# 11ethernetGbit.net
KiCad netlist of a schematic drawn in Altium Designer
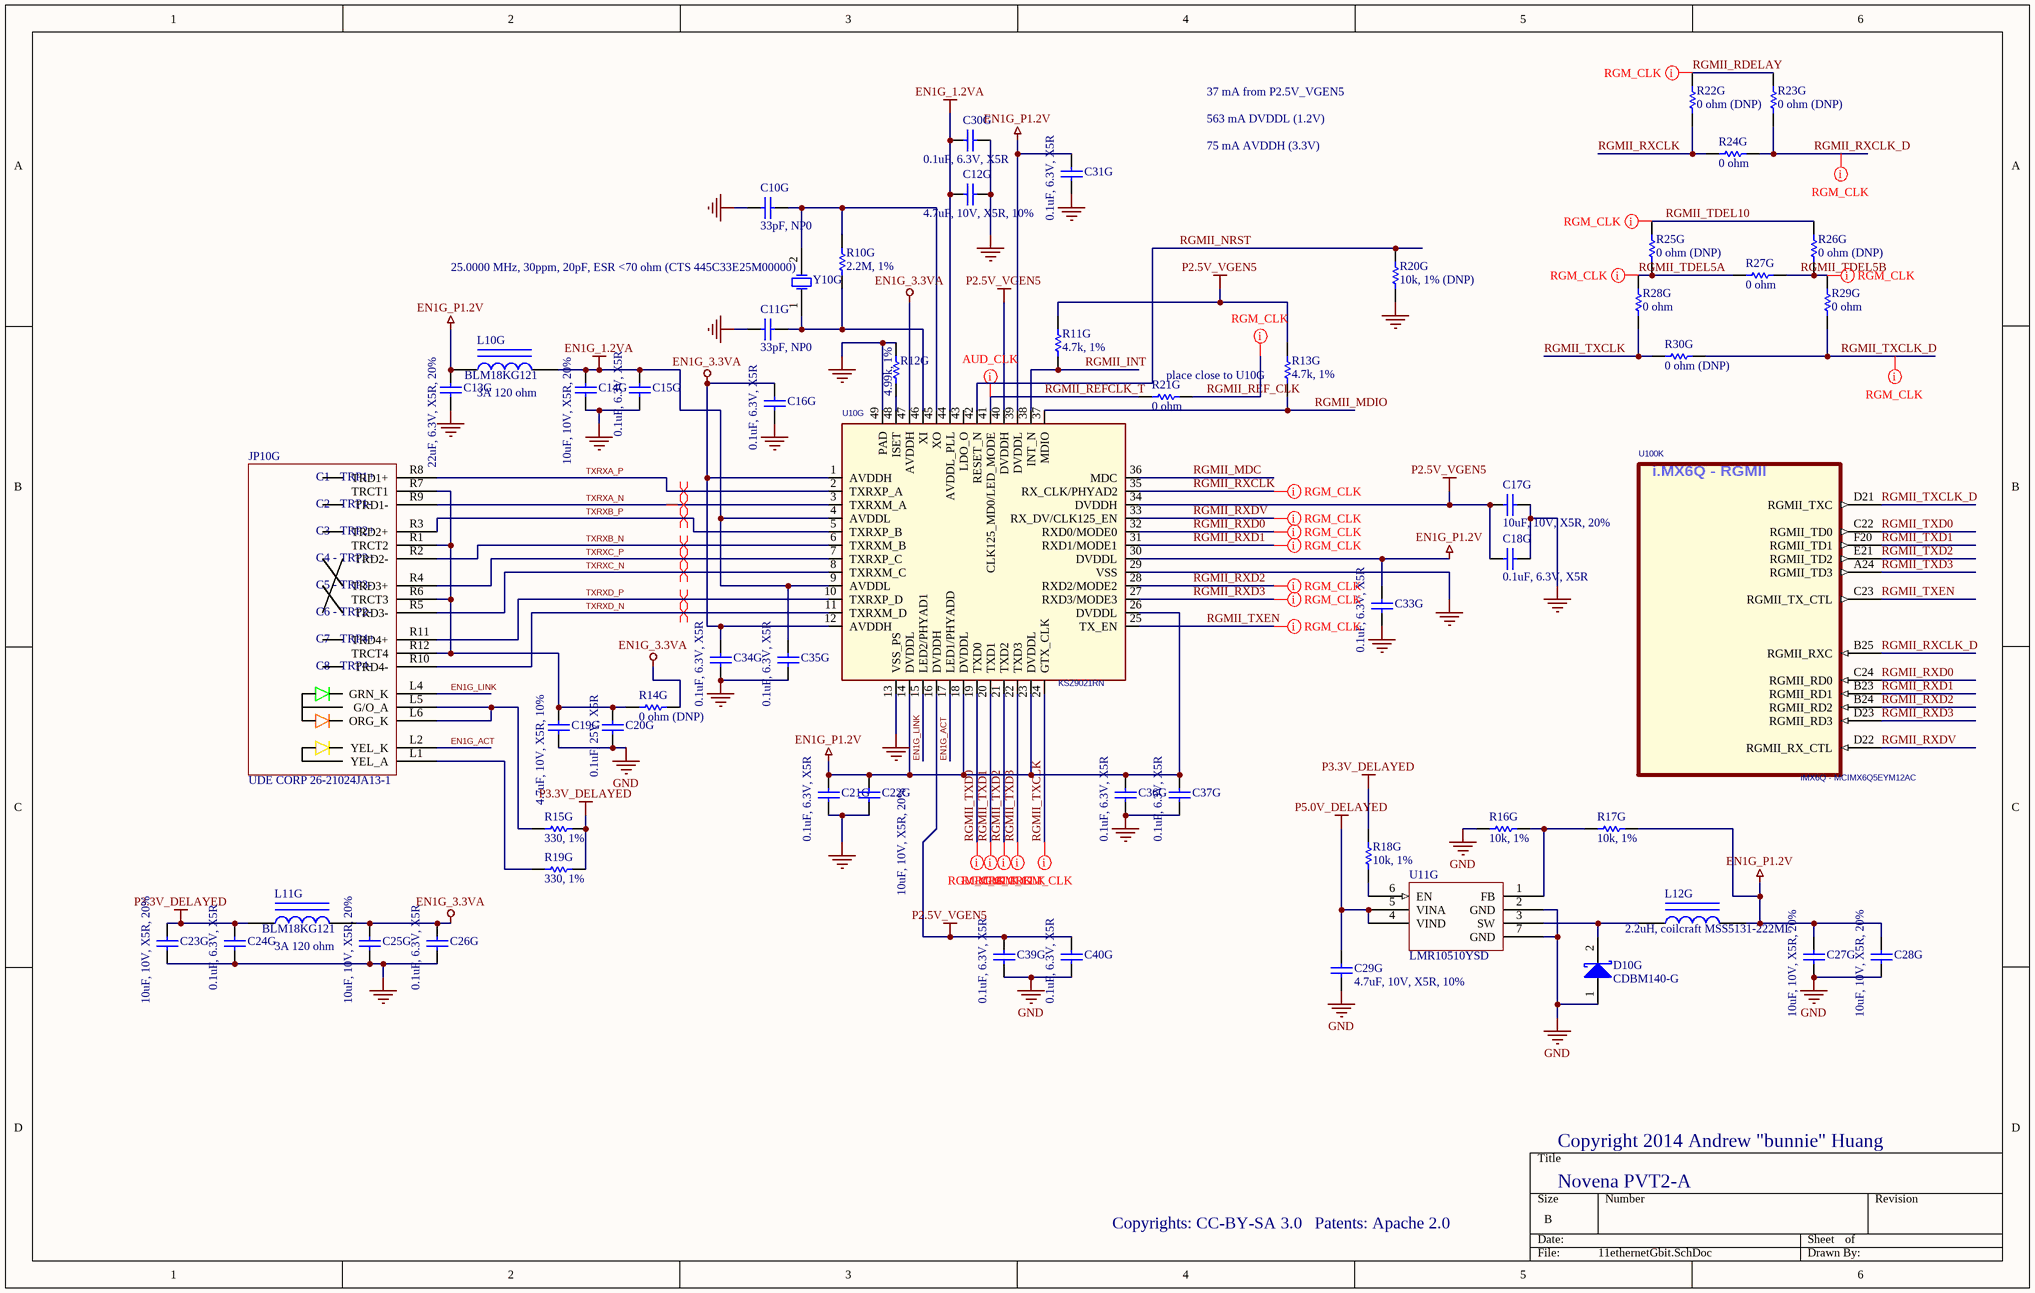
[diagram p0: 11ethernetGbit.SchDoc]

(export (version "E")
  (design (tool "Eeschema 10.0.6"))
  (components
    (comp (ref "C10G")
      (value "33pF, NP0")
      (footprint "CAPC1005N")
      (description "Capacitor (Semiconductor SIM Model)")
      (fields (field (name "PUBLISHER") "Altium Limited"))
      (libsource (lib "Miscellaneous Devices") (part "Cap Semi"))
    )
    (comp (ref "C11G")
      (value "33pF, NP0")
      (footprint "CAPC1005N")
      (description "Capacitor (Semiconductor SIM Model)")
      (fields (field (name "PUBLISHER") "Altium Limited"))
      (libsource (lib "Miscellaneous Devices") (part "Cap Semi"))
    )
    (comp (ref "C12G")
      (value "4.7uF, 10V, X5R, 10%")
      (footprint "CAPC1608N")
      (description "Capacitor (Semiconductor SIM Model)")
      (fields (field (name "PUBLISHER") "Altium Limited"))
      (libsource (lib "Miscellaneous Devices") (part "Cap Semi"))
    )
    (comp (ref "C13G")
      (value "22uF, 6.3V, X5R, 20%")
      (footprint "CAPC1608N_HD")
      (description "Capacitor (Semiconductor SIM Model)")
      (fields (field (name "PUBLISHER") "Altium Limited"))
      (libsource (lib "Miscellaneous Devices") (part "Cap Semi"))
    )
    (comp (ref "C14G")
      (value "10uF, 10V, X5R, 20%")
      (footprint "CAPC1608N")
      (description "Capacitor (Semiconductor SIM Model)")
      (fields (field (name "PUBLISHER") "Altium Limited"))
      (libsource (lib "Miscellaneous Devices") (part "Cap Semi"))
    )
    (comp (ref "C15G")
      (value "0.1uF, 6.3V, X5R")
      (footprint "CAPC0603N_B")
      (description "Capacitor (Semiconductor SIM Model)")
      (fields (field (name "PUBLISHER") "Altium Limited"))
      (libsource (lib "Miscellaneous Devices") (part "Cap Semi"))
    )
    (comp (ref "C16G")
      (value "0.1uF, 6.3V, X5R")
      (footprint "CAPC0603N_B")
      (description "Capacitor (Semiconductor SIM Model)")
      (fields (field (name "PUBLISHER") "Altium Limited"))
      (libsource (lib "Miscellaneous Devices") (part "Cap Semi"))
    )
    (comp (ref "C17G")
      (value "10uF, 10V, X5R, 20%")
      (footprint "CAPC1608N")
      (description "Capacitor (Semiconductor SIM Model)")
      (fields (field (name "PUBLISHER") "Altium Limited"))
      (libsource (lib "Miscellaneous Devices") (part "Cap Semi"))
    )
    (comp (ref "C18G")
      (value "0.1uF, 6.3V, X5R")
      (footprint "CAPC0603N_B")
      (description "Capacitor (Semiconductor SIM Model)")
      (fields (field (name "PUBLISHER") "Altium Limited"))
      (libsource (lib "Miscellaneous Devices") (part "Cap Semi"))
    )
    (comp (ref "C19G")
      (value "4.7uF, 10V, X5R, 10%")
      (footprint "CAPC1608N")
      (description "Capacitor (Semiconductor SIM Model)")
      (fields (field (name "PUBLISHER") "Altium Limited"))
      (libsource (lib "Miscellaneous Devices") (part "Cap Semi"))
    )
    (comp (ref "C20G")
      (value "0.1uF, 25V, X5R")
      (footprint "CAPC1005N")
      (description "Capacitor (Semiconductor SIM Model)")
      (fields (field (name "PUBLISHER") "Altium Limited"))
      (libsource (lib "Miscellaneous Devices") (part "Cap Semi"))
    )
    (comp (ref "C21G")
      (value "0.1uF, 6.3V, X5R")
      (footprint "CAPC0603N_B")
      (description "Capacitor (Semiconductor SIM Model)")
      (fields (field (name "PUBLISHER") "Altium Limited"))
      (libsource (lib "Miscellaneous Devices") (part "Cap Semi"))
    )
    (comp (ref "C22G")
      (value "10uF, 10V, X5R, 20%")
      (footprint "CAPC1608N")
      (description "Capacitor (Semiconductor SIM Model)")
      (fields (field (name "PUBLISHER") "Altium Limited"))
      (libsource (lib "Miscellaneous Devices") (part "Cap Semi"))
    )
    (comp (ref "C23G")
      (value "10uF, 10V, X5R, 20%")
      (footprint "CAPC1608N")
      (description "Capacitor (Semiconductor SIM Model)")
      (fields (field (name "PUBLISHER") "Altium Limited"))
      (libsource (lib "Miscellaneous Devices") (part "Cap Semi"))
    )
    (comp (ref "C24G")
      (value "0.1uF, 6.3V, X5R")
      (footprint "CAPC0603N_B")
      (description "Capacitor (Semiconductor SIM Model)")
      (fields (field (name "PUBLISHER") "Altium Limited"))
      (libsource (lib "Miscellaneous Devices") (part "Cap Semi"))
    )
    (comp (ref "C25G")
      (value "10uF, 10V, X5R, 20%")
      (footprint "CAPC1608N")
      (description "Capacitor (Semiconductor SIM Model)")
      (fields (field (name "PUBLISHER") "Altium Limited"))
      (libsource (lib "Miscellaneous Devices") (part "Cap Semi"))
    )
    (comp (ref "C26G")
      (value "0.1uF, 6.3V, X5R")
      (footprint "CAPC0603N_B")
      (description "Capacitor (Semiconductor SIM Model)")
      (fields (field (name "PUBLISHER") "Altium Limited"))
      (libsource (lib "Miscellaneous Devices") (part "Cap Semi"))
    )
    (comp (ref "C27G")
      (value "10uF, 10V, X5R, 20%")
      (footprint "CAPC1608N")
      (description "Capacitor (Semiconductor SIM Model)")
      (fields (field (name "PUBLISHER") "Altium Limited"))
      (libsource (lib "Miscellaneous Devices") (part "Cap Semi"))
    )
    (comp (ref "C28G")
      (value "10uF, 10V, X5R, 20%")
      (footprint "CAPC1608N")
      (description "Capacitor (Semiconductor SIM Model)")
      (fields (field (name "PUBLISHER") "Altium Limited"))
      (libsource (lib "Miscellaneous Devices") (part "Cap Semi"))
    )
    (comp (ref "C29G")
      (value "4.7uF, 10V, X5R, 10%")
      (footprint "CAPC1608N")
      (description "Capacitor (Semiconductor SIM Model)")
      (fields (field (name "PUBLISHER") "Altium Limited"))
      (libsource (lib "Miscellaneous Devices") (part "Cap Semi"))
    )
    (comp (ref "C30G")
      (value "0.1uF, 6.3V, X5R")
      (footprint "CAPC0603N_B")
      (description "Capacitor (Semiconductor SIM Model)")
      (fields (field (name "PUBLISHER") "Altium Limited"))
      (libsource (lib "Miscellaneous Devices") (part "Cap Semi"))
    )
    (comp (ref "C31G")
      (value "0.1uF, 6.3V, X5R")
      (footprint "CAPC0603N_B")
      (description "Capacitor (Semiconductor SIM Model)")
      (fields (field (name "PUBLISHER") "Altium Limited"))
      (libsource (lib "Miscellaneous Devices") (part "Cap Semi"))
    )
    (comp (ref "C33G")
      (value "0.1uF, 6.3V, X5R")
      (footprint "CAPC0603N_B")
      (description "Capacitor (Semiconductor SIM Model)")
      (fields (field (name "PUBLISHER") "Altium Limited"))
      (libsource (lib "Miscellaneous Devices") (part "Cap Semi"))
    )
    (comp (ref "C34G")
      (value "0.1uF, 6.3V, X5R")
      (footprint "CAPC0603N_B")
      (description "Capacitor (Semiconductor SIM Model)")
      (fields (field (name "PUBLISHER") "Altium Limited"))
      (libsource (lib "Miscellaneous Devices") (part "Cap Semi"))
    )
    (comp (ref "C35G")
      (value "0.1uF, 6.3V, X5R")
      (footprint "CAPC0603N_B")
      (description "Capacitor (Semiconductor SIM Model)")
      (fields (field (name "PUBLISHER") "Altium Limited"))
      (libsource (lib "Miscellaneous Devices") (part "Cap Semi"))
    )
    (comp (ref "C36G")
      (value "0.1uF, 6.3V, X5R")
      (footprint "CAPC0603N_B")
      (description "Capacitor (Semiconductor SIM Model)")
      (fields (field (name "PUBLISHER") "Altium Limited"))
      (libsource (lib "Miscellaneous Devices") (part "Cap Semi"))
    )
    (comp (ref "C37G")
      (value "0.1uF, 6.3V, X5R")
      (footprint "CAPC0603N_B")
      (description "Capacitor (Semiconductor SIM Model)")
      (fields (field (name "PUBLISHER") "Altium Limited"))
      (libsource (lib "Miscellaneous Devices") (part "Cap Semi"))
    )
    (comp (ref "C39G")
      (value "0.1uF, 6.3V, X5R")
      (footprint "CAPC0603N_B")
      (description "Capacitor (Semiconductor SIM Model)")
      (fields (field (name "PUBLISHER") "Altium Limited"))
      (libsource (lib "Miscellaneous Devices") (part "Cap Semi"))
    )
    (comp (ref "C40G")
      (value "0.1uF, 6.3V, X5R")
      (footprint "CAPC0603N_B")
      (description "Capacitor (Semiconductor SIM Model)")
      (fields (field (name "PUBLISHER") "Altium Limited"))
      (libsource (lib "Miscellaneous Devices") (part "Cap Semi"))
    )
    (comp (ref "D10G")
      (value "CDBM140-G")
      (footprint "SOD123")
      (description "Schottky Diode")
      (fields (field (name "PUBLISHER") "Altium Limited"))
      (libsource (lib "Miscellaneous Devices") (part "D Schottky"))
    )
    (comp (ref "JP10G")
      (value "UDE CORP 26-21024JA13-1")
      (footprint "UDE_CORP_26-21024JA13-1")
      (description "10/100/1000BT + magnetics, symmetric, tab up, with LEDs")
      (libsource (lib "commonsch") (part "UDE_CORP_26-21024JA13-1"))
    )
    (comp (ref "L10G")
      (value "BLM18KG121")
      (footprint "INDC1608AN")
      (description "Magnetic-Core Inductor")
      (fields (field (name "ALTIUM_VALUE") "3A 120 ohm") (field (name "PUBLISHER") "Altium Limited"))
      (libsource (lib "Miscellaneous Devices") (part "Inductor Iron"))
    )
    (comp (ref "L11G")
      (value "BLM18KG121")
      (footprint "INDC1608AN")
      (description "Magnetic-Core Inductor")
      (fields (field (name "ALTIUM_VALUE") "3A 120 ohm") (field (name "PUBLISHER") "Altium Limited"))
      (libsource (lib "Miscellaneous Devices") (part "Inductor Iron"))
    )
    (comp (ref "L12G")
      (value "2.2uH, coilcraft MSS5131-222ML")
      (footprint "COILCRAFT_MSS5121")
      (description "Magnetic-Core Inductor")
      (fields (field (name "PUBLISHER") "Altium Limited"))
      (libsource (lib "Miscellaneous Devices") (part "Inductor Iron"))
    )
    (comp (ref "R10G")
      (value "2.2M, 1%")
      (footprint "RESC1005N")
      (description "Resistor")
      (fields (field (name "PUBLISHER") "Altium Limited"))
      (libsource (lib "Miscellaneous Devices") (part "Res1"))
    )
    (comp (ref "R11G")
      (value "4.7k, 1%")
      (footprint "RESC1005N")
      (description "Resistor")
      (fields (field (name "PUBLISHER") "Altium Limited"))
      (libsource (lib "Miscellaneous Devices") (part "Res1"))
    )
    (comp (ref "R12G")
      (value "4.99k, 1%")
      (footprint "RESC1005N")
      (description "Resistor")
      (fields (field (name "PUBLISHER") "Altium Limited"))
      (libsource (lib "Miscellaneous Devices") (part "Res1"))
    )
    (comp (ref "R13G")
      (value "4.7k, 1%")
      (footprint "RESC1005N")
      (description "Resistor")
      (fields (field (name "PUBLISHER") "Altium Limited"))
      (libsource (lib "Miscellaneous Devices") (part "Res1"))
    )
    (comp (ref "R14G")
      (value "0 ohm (DNP)")
      (footprint "RESC1005N")
      (description "Resistor")
      (fields (field (name "PUBLISHER") "Altium Limited"))
      (libsource (lib "Miscellaneous Devices") (part "Res1"))
    )
    (comp (ref "R15G")
      (value "330, 1%")
      (footprint "RESC1005N")
      (description "Resistor")
      (fields (field (name "PUBLISHER") "Altium Limited"))
      (libsource (lib "Miscellaneous Devices") (part "Res1"))
    )
    (comp (ref "R16G")
      (value "10k, 1%")
      (footprint "RESC1005N")
      (description "Resistor")
      (fields (field (name "PUBLISHER") "Altium Limited"))
      (libsource (lib "Miscellaneous Devices") (part "Res1"))
    )
    (comp (ref "R17G")
      (value "10k, 1%")
      (footprint "RESC1005N")
      (description "Resistor")
      (fields (field (name "PUBLISHER") "Altium Limited"))
      (libsource (lib "Miscellaneous Devices") (part "Res1"))
    )
    (comp (ref "R18G")
      (value "10k, 1%")
      (footprint "RESC1005N")
      (description "Resistor")
      (fields (field (name "PUBLISHER") "Altium Limited"))
      (libsource (lib "Miscellaneous Devices") (part "Res1"))
    )
    (comp (ref "R19G")
      (value "330, 1%")
      (footprint "RESC1005N")
      (description "Resistor")
      (fields (field (name "PUBLISHER") "Altium Limited"))
      (libsource (lib "Miscellaneous Devices") (part "Res1"))
    )
    (comp (ref "R20G")
      (value "10k, 1% (DNP)")
      (footprint "RESC1005N")
      (description "Resistor")
      (fields (field (name "PUBLISHER") "Altium Limited"))
      (libsource (lib "Miscellaneous Devices") (part "Res1"))
    )
    (comp (ref "R21G")
      (value "0 ohm")
      (footprint "RESC1005N")
      (description "Resistor")
      (fields (field (name "PUBLISHER") "Altium Limited"))
      (libsource (lib "Miscellaneous Devices") (part "Res1"))
    )
    (comp (ref "R22G")
      (value "0 ohm (DNP)")
      (footprint "RESC1005N")
      (description "Resistor")
      (fields (field (name "PUBLISHER") "Altium Limited"))
      (libsource (lib "Miscellaneous Devices") (part "Res1"))
    )
    (comp (ref "R23G")
      (value "0 ohm (DNP)")
      (footprint "RESC1005N")
      (description "Resistor")
      (fields (field (name "PUBLISHER") "Altium Limited"))
      (libsource (lib "Miscellaneous Devices") (part "Res1"))
    )
    (comp (ref "R24G")
      (value "0 ohm")
      (footprint "RESC1005N")
      (description "Resistor")
      (fields (field (name "PUBLISHER") "Altium Limited"))
      (libsource (lib "Miscellaneous Devices") (part "Res1"))
    )
    (comp (ref "R25G")
      (value "0 ohm (DNP)")
      (footprint "RESC1005N")
      (description "Resistor")
      (fields (field (name "PUBLISHER") "Altium Limited"))
      (libsource (lib "Miscellaneous Devices") (part "Res1"))
    )
    (comp (ref "R26G")
      (value "0 ohm (DNP)")
      (footprint "RESC1005N")
      (description "Resistor")
      (fields (field (name "PUBLISHER") "Altium Limited"))
      (libsource (lib "Miscellaneous Devices") (part "Res1"))
    )
    (comp (ref "R27G")
      (value "0 ohm")
      (footprint "RESC1005N")
      (description "Resistor")
      (fields (field (name "PUBLISHER") "Altium Limited"))
      (libsource (lib "Miscellaneous Devices") (part "Res1"))
    )
    (comp (ref "R28G")
      (value "0 ohm")
      (footprint "RESC1005N")
      (description "Resistor")
      (fields (field (name "PUBLISHER") "Altium Limited"))
      (libsource (lib "Miscellaneous Devices") (part "Res1"))
    )
    (comp (ref "R29G")
      (value "0 ohm")
      (footprint "RESC1005N")
      (description "Resistor")
      (fields (field (name "PUBLISHER") "Altium Limited"))
      (libsource (lib "Miscellaneous Devices") (part "Res1"))
    )
    (comp (ref "R30G")
      (value "0 ohm (DNP)")
      (footprint "RESC1005N")
      (description "Resistor")
      (fields (field (name "PUBLISHER") "Altium Limited"))
      (libsource (lib "Miscellaneous Devices") (part "Res1"))
    )
    (comp (ref "U10G")
      (value "KSZ9021RN")
      (footprint "MICREL_QFN48_EP")
      (description "Gigabit Ethernet PHY")
      (libsource (lib "*") (part "KSZ9021_0"))
    )
    (comp (ref "U11G")
      (value "LMR10510YSD")
      (footprint "SON95P300X300X80-7V")
      (description "NatSemi 1.5A step-down regulator in LLP")
      (libsource (lib "commonsch") (part "LMR10515XSD"))
    )
    (comp (ref "U100")
      (value "iMX6Q - MCIMX6Q5EYM12AC")
      (footprint "FREESCALE_BGA624C80P25X25_2100X2100X216")
      (description "PLACEHOLDER FOR FREESCALE PART NUMBER PMCIMX6Q6VV1A.")
      (libsource (lib "*") (part "PCIMX6Q6VV1A"))
    )
    (comp (ref "Y10G")
      (value "25.0000 MHz, 30ppm, 20pF, ESR <70 ohm (CTS 445C33E25M00000)")
      (footprint "NDK_NX5032A")
      (description "Crystal Oscillator")
      (fields (field (name "PUBLISHER") "Altium Limited"))
      (libsource (lib "Miscellaneous Devices") (part "XTAL"))
    )
  )
  (nets
    (net (code "1") (name "/EN1G_ACT") (class "Default")
      (node (ref "JP10G") (pin "L2") (pinfunction "YEL_K_L2") (pintype "passive"))
      (node (ref "U10G") (pin "17") (pinfunction "LED1/PHYADD_17") (pintype "passive"))
    )
    (net (code "2") (name "/EN1G_LINK") (class "Default")
      (node (ref "JP10G") (pin "L4") (pinfunction "GRN_K_L4") (pintype "passive"))
      (node (ref "U10G") (pin "15") (pinfunction "LED2/PHYAD1_15") (pintype "passive"))
    )
    (net (code "3") (name "/RGMII_INT") (class "Default")
      (node (ref "R11G") (pin "1") (pinfunction "1_1") (pintype "passive"))
      (node (ref "U10G") (pin "38") (pinfunction "INT_N_38") (pintype "passive"))
    )
    (net (code "4") (name "/RGMII_MDC") (class "Default")
      (node (ref "U10G") (pin "36") (pinfunction "MDC_36") (pintype "passive"))
    )
    (net (code "5") (name "/RGMII_MDIO") (class "Default")
      (node (ref "R13G") (pin "1") (pinfunction "1_1") (pintype "passive"))
      (node (ref "U10G") (pin "37") (pinfunction "MDIO_37") (pintype "passive"))
    )
    (net (code "6") (name "/RGMII_NRST") (class "Default")
      (node (ref "R20G") (pin "2") (pinfunction "2_2") (pintype "passive"))
      (node (ref "U10G") (pin "42") (pinfunction "RESET_N_42") (pintype "passive"))
    )
    (net (code "7") (name "/RGMII_RDELAY") (class "Default")
      (node (ref "R22G") (pin "2") (pinfunction "2_2") (pintype "passive"))
      (node (ref "R23G") (pin "2") (pinfunction "2_2") (pintype "passive"))
    )
    (net (code "8") (name "/RGMII_REFCLK_T") (class "Default")
      (node (ref "R21G") (pin "1") (pinfunction "1_1") (pintype "passive"))
      (node (ref "U10G") (pin "41") (pinfunction "CLK125_MD0/LED_MODE_41") (pintype "passive"))
    )
    (net (code "9") (name "/RGMII_REF_CLK") (class "Default")
      (node (ref "R21G") (pin "2") (pinfunction "2_2") (pintype "passive"))
    )
    (net (code "10") (name "/RGMII_RXCLK") (class "Default")
      (node (ref "R22G") (pin "1") (pinfunction "1_1") (pintype "passive"))
      (node (ref "R24G") (pin "1") (pinfunction "1_1") (pintype "passive"))
      (node (ref "U10G") (pin "35") (pinfunction "RX_CLK/PHYAD2_35") (pintype "passive"))
    )
    (net (code "11") (name "/RGMII_RXCLK_D") (class "Default")
      (node (ref "R23G") (pin "1") (pinfunction "1_1") (pintype "passive"))
      (node (ref "R24G") (pin "2") (pinfunction "2_2") (pintype "passive"))
      (node (ref "U100") (pin "B25") (pinfunction "RGMII_RXC_B25") (pintype "input"))
    )
    (net (code "12") (name "/RGMII_RXD0") (class "Default")
      (node (ref "U100") (pin "C24") (pinfunction "RGMII_RD0_C24") (pintype "input"))
      (node (ref "U10G") (pin "32") (pinfunction "RXD0/MODE0_32") (pintype "passive"))
    )
    (net (code "13") (name "/RGMII_RXD1") (class "Default")
      (node (ref "U100") (pin "B23") (pinfunction "RGMII_RD1_B23") (pintype "input"))
      (node (ref "U10G") (pin "31") (pinfunction "RXD1/MODE1_31") (pintype "passive"))
    )
    (net (code "14") (name "/RGMII_RXD2") (class "Default")
      (node (ref "U100") (pin "B24") (pinfunction "RGMII_RD2_B24") (pintype "input"))
      (node (ref "U10G") (pin "28") (pinfunction "RXD2/MODE2_28") (pintype "passive"))
    )
    (net (code "15") (name "/RGMII_RXD3") (class "Default")
      (node (ref "U100") (pin "D23") (pinfunction "RGMII_RD3_D23") (pintype "input"))
      (node (ref "U10G") (pin "27") (pinfunction "RXD3/MODE3_27") (pintype "passive"))
    )
    (net (code "16") (name "/RGMII_RXDV") (class "Default")
      (node (ref "U100") (pin "D22") (pinfunction "RGMII_RX_CTL_D22") (pintype "input"))
      (node (ref "U10G") (pin "33") (pinfunction "RX_DV/CLK125_EN_33") (pintype "passive"))
    )
    (net (code "17") (name "/RGMII_TDEL5A") (class "Default")
      (node (ref "R25G") (pin "1") (pinfunction "1_1") (pintype "passive"))
      (node (ref "R27G") (pin "2") (pinfunction "2_2") (pintype "passive"))
      (node (ref "R28G") (pin "2") (pinfunction "2_2") (pintype "passive"))
    )
    (net (code "18") (name "/RGMII_TDEL5B") (class "Default")
      (node (ref "R26G") (pin "1") (pinfunction "1_1") (pintype "passive"))
      (node (ref "R27G") (pin "1") (pinfunction "1_1") (pintype "passive"))
      (node (ref "R29G") (pin "2") (pinfunction "2_2") (pintype "passive"))
    )
    (net (code "19") (name "/RGMII_TDEL10") (class "Default")
      (node (ref "R25G") (pin "2") (pinfunction "2_2") (pintype "passive"))
      (node (ref "R26G") (pin "2") (pinfunction "2_2") (pintype "passive"))
    )
    (net (code "20") (name "/RGMII_TXCLK") (class "Default")
      (node (ref "R28G") (pin "1") (pinfunction "1_1") (pintype "passive"))
      (node (ref "R30G") (pin "1") (pinfunction "1_1") (pintype "passive"))
      (node (ref "U10G") (pin "24") (pinfunction "GTX_CLK_24") (pintype "passive"))
    )
    (net (code "21") (name "/RGMII_TXCLK_D") (class "Default")
      (node (ref "R29G") (pin "1") (pinfunction "1_1") (pintype "passive"))
      (node (ref "R30G") (pin "2") (pinfunction "2_2") (pintype "passive"))
      (node (ref "U100") (pin "D21") (pinfunction "RGMII_TXC_D21") (pintype "output"))
    )
    (net (code "22") (name "/RGMII_TXD0") (class "Default")
      (node (ref "U100") (pin "C22") (pinfunction "RGMII_TD0_C22") (pintype "output"))
      (node (ref "U10G") (pin "19") (pinfunction "TXD0_19") (pintype "passive"))
    )
    (net (code "23") (name "/RGMII_TXD1") (class "Default")
      (node (ref "U100") (pin "F20") (pinfunction "RGMII_TD1_F20") (pintype "output"))
      (node (ref "U10G") (pin "20") (pinfunction "TXD1_20") (pintype "passive"))
    )
    (net (code "24") (name "/RGMII_TXD2") (class "Default")
      (node (ref "U100") (pin "E21") (pinfunction "RGMII_TD2_E21") (pintype "output"))
      (node (ref "U10G") (pin "21") (pinfunction "TXD2_21") (pintype "passive"))
    )
    (net (code "25") (name "/RGMII_TXD3") (class "Default")
      (node (ref "U100") (pin "A24") (pinfunction "RGMII_TD3_A24") (pintype "output"))
      (node (ref "U10G") (pin "22") (pinfunction "TXD3_22") (pintype "passive"))
    )
    (net (code "26") (name "/RGMII_TXEN") (class "Default")
      (node (ref "U100") (pin "C23") (pinfunction "RGMII_TX_CTL_C23") (pintype "output"))
      (node (ref "U10G") (pin "25") (pinfunction "TX_EN_25") (pintype "passive"))
    )
    (net (code "27") (name "/TXRXA_N") (class "Default")
      (node (ref "JP10G") (pin "R9") (pinfunction "TRD1-_R9") (pintype "passive"))
      (node (ref "U10G") (pin "3") (pinfunction "TXRXM_A_3") (pintype "passive"))
    )
    (net (code "28") (name "/TXRXA_P") (class "Default")
      (node (ref "JP10G") (pin "R8") (pinfunction "TRD1+_R8") (pintype "passive"))
      (node (ref "U10G") (pin "2") (pinfunction "TXRXP_A_2") (pintype "passive"))
    )
    (net (code "29") (name "/TXRXB_N") (class "Default")
      (node (ref "JP10G") (pin "R2") (pinfunction "TRD2-_R2") (pintype "passive"))
      (node (ref "U10G") (pin "6") (pinfunction "TXRXM_B_6") (pintype "passive"))
    )
    (net (code "30") (name "/TXRXB_P") (class "Default")
      (node (ref "JP10G") (pin "R3") (pinfunction "TRD2+_R3") (pintype "passive"))
      (node (ref "U10G") (pin "5") (pinfunction "TXRXP_B_5") (pintype "passive"))
    )
    (net (code "31") (name "/TXRXC_N") (class "Default")
      (node (ref "JP10G") (pin "R5") (pinfunction "TRD3-_R5") (pintype "passive"))
      (node (ref "U10G") (pin "8") (pinfunction "TXRXM_C_8") (pintype "passive"))
    )
    (net (code "32") (name "/TXRXC_P") (class "Default")
      (node (ref "JP10G") (pin "R4") (pinfunction "TRD3+_R4") (pintype "passive"))
      (node (ref "U10G") (pin "7") (pinfunction "TXRXP_C_7") (pintype "passive"))
    )
    (net (code "33") (name "/TXRXD_N") (class "Default")
      (node (ref "JP10G") (pin "R10") (pinfunction "TRD4-_R10") (pintype "passive"))
      (node (ref "U10G") (pin "11") (pinfunction "TXRXM_D_11") (pintype "passive"))
    )
    (net (code "34") (name "/TXRXD_P") (class "Default")
      (node (ref "JP10G") (pin "R11") (pinfunction "TRD4+_R11") (pintype "passive"))
      (node (ref "U10G") (pin "10") (pinfunction "TXRXP_D_10") (pintype "passive"))
    )
    (net (code "35") (name "EN1G_1.2VA") (class "Default")
      (node (ref "C12G") (pin "1") (pinfunction "1_1") (pintype "passive"))
      (node (ref "C14G") (pin "1") (pinfunction "1_1") (pintype "passive"))
      (node (ref "C15G") (pin "1") (pinfunction "1_1") (pintype "passive"))
      (node (ref "C30G") (pin "2") (pinfunction "2_2") (pintype "passive"))
      (node (ref "C35G") (pin "1") (pinfunction "1_1") (pintype "passive"))
      (node (ref "L10G") (pin "2") (pinfunction "2_2") (pintype "passive"))
      (node (ref "U10G") (pin "4") (pinfunction "AVDDL_4") (pintype "passive"))
      (node (ref "U10G") (pin "44") (pinfunction "AVDDL_PLL_44") (pintype "passive"))
      (node (ref "U10G") (pin "9") (pinfunction "AVDDL_9") (pintype "passive"))
    )
    (net (code "36") (name "EN1G_3.3VA") (class "Default")
      (node (ref "C16G") (pin "1") (pinfunction "1_1") (pintype "passive"))
      (node (ref "C25G") (pin "1") (pinfunction "1_1") (pintype "passive"))
      (node (ref "C26G") (pin "1") (pinfunction "1_1") (pintype "passive"))
      (node (ref "C34G") (pin "1") (pinfunction "1_1") (pintype "passive"))
      (node (ref "L11G") (pin "2") (pinfunction "2_2") (pintype "passive"))
      (node (ref "R14G") (pin "2") (pinfunction "2_2") (pintype "passive"))
      (node (ref "U10G") (pin "1") (pinfunction "AVDDH_1") (pintype "passive"))
      (node (ref "U10G") (pin "12") (pinfunction "AVDDH_12") (pintype "passive"))
      (node (ref "U10G") (pin "47") (pinfunction "AVDDH_47") (pintype "passive"))
    )
    (net (code "37") (name "EN1G_P1.2V") (class "Default")
      (node (ref "C13G") (pin "1") (pinfunction "1_1") (pintype "passive"))
      (node (ref "C21G") (pin "1") (pinfunction "1_1") (pintype "passive"))
      (node (ref "C22G") (pin "1") (pinfunction "1_1") (pintype "passive"))
      (node (ref "C27G") (pin "2") (pinfunction "2_2") (pintype "passive"))
      (node (ref "C28G") (pin "2") (pinfunction "2_2") (pintype "passive"))
      (node (ref "C31G") (pin "1") (pinfunction "1_1") (pintype "passive"))
      (node (ref "C33G") (pin "1") (pinfunction "1_1") (pintype "passive"))
      (node (ref "C36G") (pin "1") (pinfunction "1_1") (pintype "passive"))
      (node (ref "C37G") (pin "1") (pinfunction "1_1") (pintype "passive"))
      (node (ref "L10G") (pin "1") (pinfunction "1_1") (pintype "passive"))
      (node (ref "L12G") (pin "2") (pinfunction "2_2") (pintype "passive"))
      (node (ref "R17G") (pin "1") (pinfunction "1_1") (pintype "passive"))
      (node (ref "U10G") (pin "14") (pinfunction "DVDDL_14") (pintype "passive"))
      (node (ref "U10G") (pin "18") (pinfunction "DVDDL_18") (pintype "passive"))
      (node (ref "U10G") (pin "23") (pinfunction "DVDDL_23") (pintype "passive"))
      (node (ref "U10G") (pin "26") (pinfunction "DVDDL_26") (pintype "passive"))
      (node (ref "U10G") (pin "30") (pinfunction "DVDDL_30") (pintype "passive"))
      (node (ref "U10G") (pin "39") (pinfunction "DVDDL_39") (pintype "passive"))
    )
    (net (code "38") (name "GND") (class "Default")
      (node (ref "C10G") (pin "1") (pinfunction "1_1") (pintype "passive"))
      (node (ref "C11G") (pin "1") (pinfunction "1_1") (pintype "passive"))
      (node (ref "C12G") (pin "2") (pinfunction "2_2") (pintype "passive"))
      (node (ref "C13G") (pin "2") (pinfunction "2_2") (pintype "passive"))
      (node (ref "C14G") (pin "2") (pinfunction "2_2") (pintype "passive"))
      (node (ref "C15G") (pin "2") (pinfunction "2_2") (pintype "passive"))
      (node (ref "C16G") (pin "2") (pinfunction "2_2") (pintype "passive"))
      (node (ref "C17G") (pin "2") (pinfunction "2_2") (pintype "passive"))
      (node (ref "C18G") (pin "2") (pinfunction "2_2") (pintype "passive"))
      (node (ref "C19G") (pin "2") (pinfunction "2_2") (pintype "passive"))
      (node (ref "C20G") (pin "2") (pinfunction "2_2") (pintype "passive"))
      (node (ref "C21G") (pin "2") (pinfunction "2_2") (pintype "passive"))
      (node (ref "C22G") (pin "2") (pinfunction "2_2") (pintype "passive"))
      (node (ref "C23G") (pin "2") (pinfunction "2_2") (pintype "passive"))
      (node (ref "C24G") (pin "2") (pinfunction "2_2") (pintype "passive"))
      (node (ref "C25G") (pin "2") (pinfunction "2_2") (pintype "passive"))
      (node (ref "C26G") (pin "2") (pinfunction "2_2") (pintype "passive"))
      (node (ref "C27G") (pin "1") (pinfunction "1_1") (pintype "passive"))
      (node (ref "C28G") (pin "1") (pinfunction "1_1") (pintype "passive"))
      (node (ref "C29G") (pin "2") (pinfunction "2_2") (pintype "passive"))
      (node (ref "C30G") (pin "1") (pinfunction "1_1") (pintype "passive"))
      (node (ref "C31G") (pin "2") (pinfunction "2_2") (pintype "passive"))
      (node (ref "C33G") (pin "2") (pinfunction "2_2") (pintype "passive"))
      (node (ref "C34G") (pin "2") (pinfunction "2_2") (pintype "passive"))
      (node (ref "C35G") (pin "2") (pinfunction "2_2") (pintype "passive"))
      (node (ref "C36G") (pin "2") (pinfunction "2_2") (pintype "passive"))
      (node (ref "C37G") (pin "2") (pinfunction "2_2") (pintype "passive"))
      (node (ref "C39G") (pin "2") (pinfunction "2_2") (pintype "passive"))
      (node (ref "C40G") (pin "2") (pinfunction "2_2") (pintype "passive"))
      (node (ref "D10G") (pin "1") (pinfunction "A_1") (pintype "passive"))
      (node (ref "R12G") (pin "2") (pinfunction "2_2") (pintype "passive"))
      (node (ref "R16G") (pin "2") (pinfunction "2_2") (pintype "passive"))
      (node (ref "R20G") (pin "1") (pinfunction "1_1") (pintype "passive"))
      (node (ref "U10G") (pin "13") (pinfunction "VSS_PS_13") (pintype "passive"))
      (node (ref "U10G") (pin "29") (pinfunction "VSS_29") (pintype "passive"))
      (node (ref "U10G") (pin "49") (pinfunction "PAD_49") (pintype "passive"))
      (node (ref "U11G") (pin "2") (pinfunction "GND_2") (pintype "power_in"))
      (node (ref "U11G") (pin "7") (pinfunction "GND_7") (pintype "power_in"))
    )
    (net (code "39") (name "Net-(D10G-K)") (class "Default")
      (node (ref "D10G") (pin "2") (pinfunction "K_2") (pintype "passive"))
      (node (ref "L12G") (pin "1") (pinfunction "1_1") (pintype "passive"))
      (node (ref "U11G") (pin "3") (pinfunction "SW_3") (pintype "passive"))
    )
    (net (code "40") (name "Net-(JP10G-G{slash}O_A)") (class "Default")
      (node (ref "JP10G") (pin "L5") (pinfunction "G/O_A_L5") (pintype "passive"))
      (node (ref "JP10G") (pin "L6") (pinfunction "ORG_K_L6") (pintype "passive"))
      (node (ref "R15G") (pin "1") (pinfunction "1_1") (pintype "passive"))
    )
    (net (code "41") (name "Net-(JP10G-TRCT1)") (class "Default")
      (node (ref "C19G") (pin "1") (pinfunction "1_1") (pintype "passive"))
      (node (ref "C20G") (pin "1") (pinfunction "1_1") (pintype "passive"))
      (node (ref "JP10G") (pin "R1") (pinfunction "TRCT2_R1") (pintype "passive"))
      (node (ref "JP10G") (pin "R12") (pinfunction "TRCT4_R12") (pintype "passive"))
      (node (ref "JP10G") (pin "R6") (pinfunction "TRCT3_R6") (pintype "passive"))
      (node (ref "JP10G") (pin "R7") (pinfunction "TRCT1_R7") (pintype "passive"))
      (node (ref "R14G") (pin "1") (pinfunction "1_1") (pintype "passive"))
    )
    (net (code "42") (name "Net-(JP10G-YEL_A)") (class "Default")
      (node (ref "JP10G") (pin "L1") (pinfunction "YEL_A_L1") (pintype "passive"))
      (node (ref "R19G") (pin "1") (pinfunction "1_1") (pintype "passive"))
    )
    (net (code "43") (name "Net-(U10G-ISET)") (class "Default")
      (node (ref "R12G") (pin "1") (pinfunction "1_1") (pintype "passive"))
      (node (ref "U10G") (pin "48") (pinfunction "ISET_48") (pintype "passive"))
    )
    (net (code "44") (name "Net-(U10G-XI)") (class "Default")
      (node (ref "C11G") (pin "2") (pinfunction "2_2") (pintype "passive"))
      (node (ref "R10G") (pin "2") (pinfunction "2_2") (pintype "passive"))
      (node (ref "U10G") (pin "46") (pinfunction "XI_46") (pintype "passive"))
      (node (ref "Y10G") (pin "1") (pinfunction "OSC1_1") (pintype "passive"))
    )
    (net (code "45") (name "Net-(U10G-XO)") (class "Default")
      (node (ref "C10G") (pin "2") (pinfunction "2_2") (pintype "passive"))
      (node (ref "R10G") (pin "1") (pinfunction "1_1") (pintype "passive"))
      (node (ref "U10G") (pin "45") (pinfunction "XO_45") (pintype "passive"))
      (node (ref "Y10G") (pin "2") (pinfunction "OSC2_2") (pintype "passive"))
    )
    (net (code "46") (name "Net-(U11G-EN)") (class "Default")
      (node (ref "R18G") (pin "1") (pinfunction "1_1") (pintype "passive"))
      (node (ref "U11G") (pin "6") (pinfunction "EN_6") (pintype "input"))
    )
    (net (code "47") (name "Net-(U11G-FB)") (class "Default")
      (node (ref "R16G") (pin "1") (pinfunction "1_1") (pintype "passive"))
      (node (ref "R17G") (pin "2") (pinfunction "2_2") (pintype "passive"))
      (node (ref "U11G") (pin "1") (pinfunction "FB_1") (pintype "passive"))
    )
    (net (code "48") (name "P2.5V_VGEN5") (class "Default")
      (node (ref "C17G") (pin "1") (pinfunction "1_1") (pintype "passive"))
      (node (ref "C18G") (pin "1") (pinfunction "1_1") (pintype "passive"))
      (node (ref "C39G") (pin "1") (pinfunction "1_1") (pintype "passive"))
      (node (ref "C40G") (pin "1") (pinfunction "1_1") (pintype "passive"))
      (node (ref "R11G") (pin "2") (pinfunction "2_2") (pintype "passive"))
      (node (ref "R13G") (pin "2") (pinfunction "2_2") (pintype "passive"))
      (node (ref "U10G") (pin "16") (pinfunction "DVDDH_16") (pintype "passive"))
      (node (ref "U10G") (pin "34") (pinfunction "DVDDH_34") (pintype "passive"))
      (node (ref "U10G") (pin "40") (pinfunction "DVDDH_40") (pintype "passive"))
    )
    (net (code "49") (name "P3.3V_DELAYED") (class "Default")
      (node (ref "C23G") (pin "1") (pinfunction "1_1") (pintype "passive"))
      (node (ref "C24G") (pin "1") (pinfunction "1_1") (pintype "passive"))
      (node (ref "L11G") (pin "1") (pinfunction "1_1") (pintype "passive"))
      (node (ref "R15G") (pin "2") (pinfunction "2_2") (pintype "passive"))
      (node (ref "R18G") (pin "2") (pinfunction "2_2") (pintype "passive"))
      (node (ref "R19G") (pin "2") (pinfunction "2_2") (pintype "passive"))
    )
    (net (code "50") (name "P5.0V_DELAYED") (class "Default")
      (node (ref "C29G") (pin "1") (pinfunction "1_1") (pintype "passive"))
      (node (ref "U11G") (pin "4") (pinfunction "VIND_4") (pintype "power_in"))
      (node (ref "U11G") (pin "5") (pinfunction "VINA_5") (pintype "power_in"))
    )
    (net (code "51") (name "unconnected-(U10G-LDO_O-Pad43)") (class "Default")
      (node (ref "U10G") (pin "43") (pinfunction "LDO_O_43") (pintype "passive"))
    )
  )
)
